# Netscale48HD_RS4850.net
KiCad netlist of a schematic drawn in Altium Designer
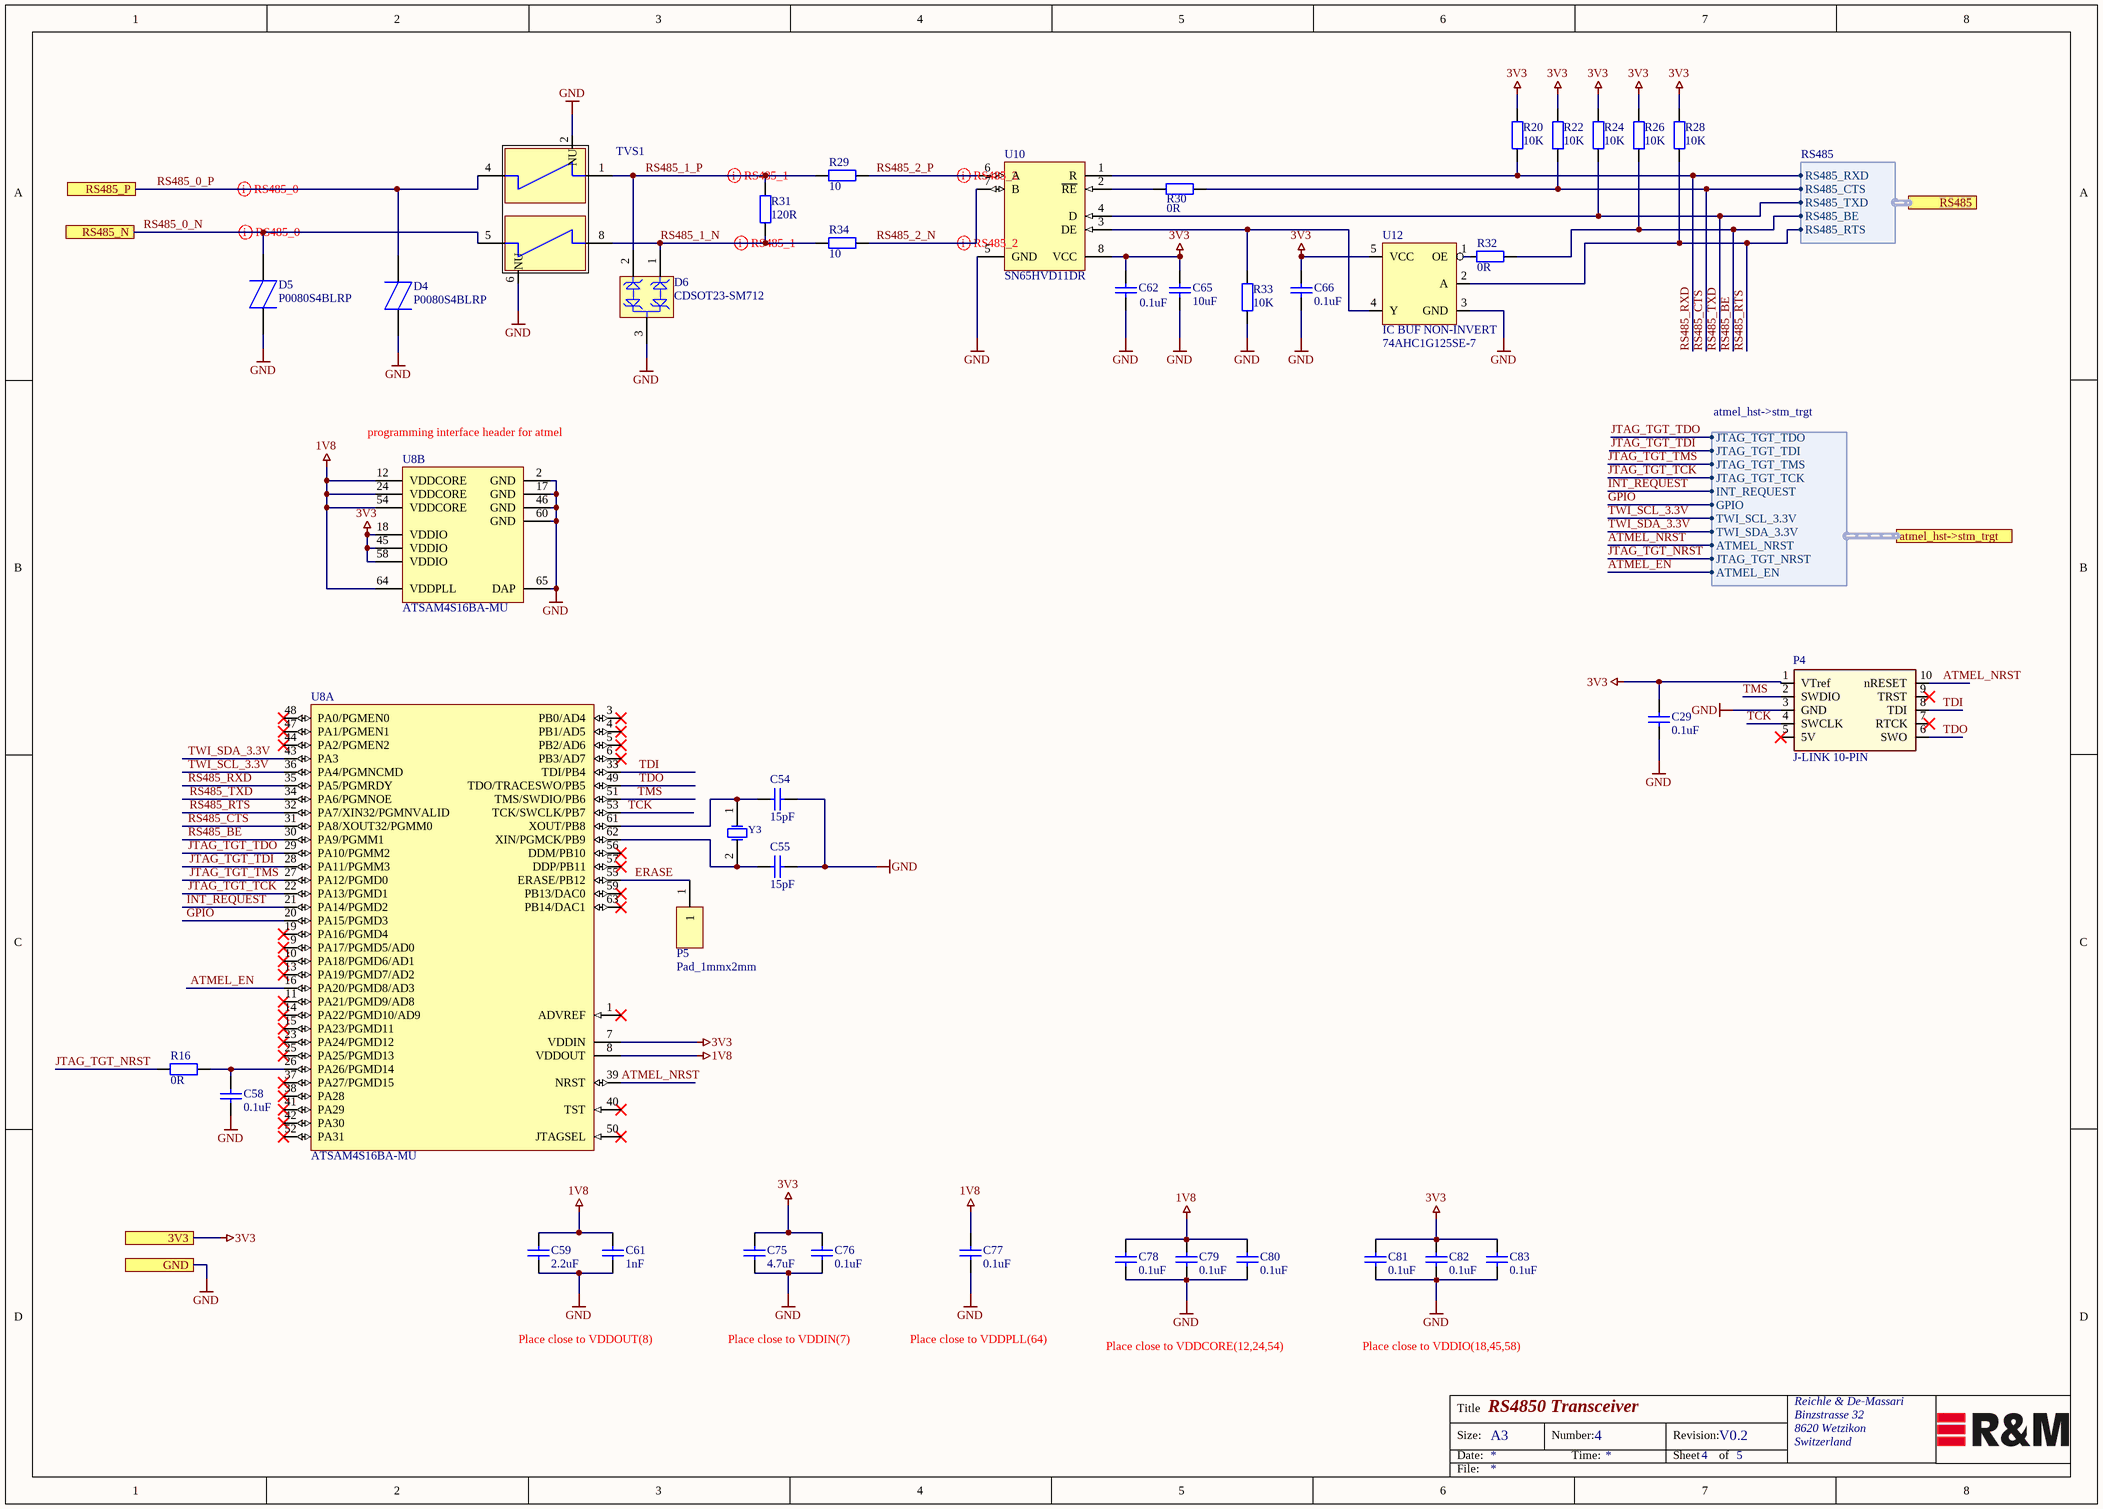
[diagram p0: Netscale48HD_RS4850.SchDoc]

(export (version "E")
  (design (tool "Eeschema 10.0.6"))
  (components
    (comp (ref "C29")
      (value "0.1uF")
      (footprint "Ceramic Capacitor 0402 EIA")
      (description "SMD/SMT WCAP-CSGP 0.1uF 0402 20% 10V MLCC")
      (fields (field (name "TOLERANCE") "20%") (field (name "VOLTAGE") "10VDC"))
      (libsource (lib "RDM_ALT_SCH") (part "Cap_0.1uF_0402"))
    )
    (comp (ref "C54")
      (value "15pF")
      (footprint "Ceramic Capacitor 0402 EIA")
      (description "Multilayer Ceramic Capacitors MLCC")
      (fields (field (name "TOLERANCE") "±1%") (field (name "VOLTAGE") "50V"))
      (libsource (lib "RDM_ALT_SCH") (part "Cap_15pF_0402"))
    )
    (comp (ref "C55")
      (value "15pF")
      (footprint "Ceramic Capacitor 0402 EIA")
      (description "Multilayer Ceramic Capacitors MLCC")
      (fields (field (name "TOLERANCE") "±1%") (field (name "VOLTAGE") "50V"))
      (libsource (lib "RDM_ALT_SCH") (part "Cap_15pF_0402"))
    )
    (comp (ref "C58")
      (value "0.1uF")
      (footprint "Ceramic Capacitor 0402 EIA")
      (description "SMD/SMT WCAP-CSGP 0.1uF 0402 20% 10V MLCC")
      (fields (field (name "TOLERANCE") "20%") (field (name "VOLTAGE") "10VDC"))
      (libsource (lib "RDM_ALT_SCH") (part "Cap_0.1uF_0402"))
    )
    (comp (ref "C59")
      (value "2.2uF")
      (footprint "Ceramic Capacitor 0402 EIA")
      (description "2.2µF ±20% 25V Ceramic Capacitor X5R 0402 (1005 Metric)")
      (fields (field (name "TOLERANCE") "±20%") (field (name "VOLTAGE") "25V"))
      (libsource (lib "RDM_ALT_SCH") (part "Cap_2.2uF_0402"))
    )
    (comp (ref "C61")
      (value "1nF")
      (footprint "Ceramic Capacitor 0402 EIA")
      (description "1000pF ±20% 50V Ceramic Capacitor X5R 0402 (1005 Metric)")
      (fields (field (name "TOLERANCE") "±20%") (field (name "VOLTAGE") "50V"))
      (libsource (lib "RDM_ALT_SCH") (part "Cap_1nF_0402"))
    )
    (comp (ref "C62")
      (value "0.1uF")
      (footprint "Ceramic Capacitor 0402 EIA")
      (description "SMD/SMT WCAP-CSGP 0.1uF 0402 20% 10V MLCC")
      (fields (field (name "TOLERANCE") "20%") (field (name "VOLTAGE") "10VDC"))
      (libsource (lib "RDM_Altium_Library") (part "Cap_0.1uF_0402"))
    )
    (comp (ref "C65")
      (value "10uF")
      (footprint "Ceramic Capacitor 0402 EIA")
      (description "Multilayer Ceramic Capacitors MLCC - SMD/SMT")
      (fields (field (name "TOLERANCE") "20%") (field (name "VOLTAGE") "10VDC"))
      (libsource (lib "RDM_Altium_Library") (part "Cap_10uF_0402"))
    )
    (comp (ref "C66")
      (value "0.1uF")
      (footprint "Ceramic Capacitor 0402 EIA")
      (description "SMD/SMT WCAP-CSGP 0.1uF 0402 20% 10V MLCC")
      (fields (field (name "TOLERANCE") "20%") (field (name "VOLTAGE") "10VDC"))
      (libsource (lib "RDM_Altium_Library") (part "Cap_0.1uF_0402"))
    )
    (comp (ref "C75")
      (value "4.7uF")
      (footprint "Ceramic Capacitor 0603 EIA")
      (description "SMD/SMT 0603 4.7uF 10volts")
      (fields (field (name "TOLERANCE") "20%") (field (name "VOLTAGE") "10VDC"))
      (libsource (lib "RDM_ALT_SCH") (part "Cap_4.7uF_0603"))
    )
    (comp (ref "C76")
      (value "0.1uF")
      (footprint "Ceramic Capacitor 0402 EIA")
      (description "SMD/SMT WCAP-CSGP 0.1uF 0402 20% 10V MLCC")
      (fields (field (name "TOLERANCE") "20%") (field (name "VOLTAGE") "10VDC"))
      (libsource (lib "RDM_ALT_SCH") (part "Cap_0.1uF_0402"))
    )
    (comp (ref "C77")
      (value "0.1uF")
      (footprint "Ceramic Capacitor 0402 EIA")
      (description "SMD/SMT WCAP-CSGP 0.1uF 0402 20% 10V MLCC")
      (fields (field (name "TOLERANCE") "20%") (field (name "VOLTAGE") "10VDC"))
      (libsource (lib "RDM_ALT_SCH") (part "Cap_0.1uF_0402"))
    )
    (comp (ref "C78")
      (value "0.1uF")
      (footprint "Ceramic Capacitor 0402 EIA")
      (description "SMD/SMT WCAP-CSGP 0.1uF 0402 20% 10V MLCC")
      (fields (field (name "TOLERANCE") "20%") (field (name "VOLTAGE") "10VDC"))
      (libsource (lib "RDM_ALT_SCH") (part "Cap_0.1uF_0402"))
    )
    (comp (ref "C79")
      (value "0.1uF")
      (footprint "Ceramic Capacitor 0402 EIA")
      (description "SMD/SMT WCAP-CSGP 0.1uF 0402 20% 10V MLCC")
      (fields (field (name "TOLERANCE") "20%") (field (name "VOLTAGE") "10VDC"))
      (libsource (lib "RDM_ALT_SCH") (part "Cap_0.1uF_0402"))
    )
    (comp (ref "C80")
      (value "0.1uF")
      (footprint "Ceramic Capacitor 0402 EIA")
      (description "SMD/SMT WCAP-CSGP 0.1uF 0402 20% 10V MLCC")
      (fields (field (name "TOLERANCE") "20%") (field (name "VOLTAGE") "10VDC"))
      (libsource (lib "RDM_ALT_SCH") (part "Cap_0.1uF_0402"))
    )
    (comp (ref "C81")
      (value "0.1uF")
      (footprint "Ceramic Capacitor 0402 EIA")
      (description "SMD/SMT WCAP-CSGP 0.1uF 0402 20% 10V MLCC")
      (fields (field (name "TOLERANCE") "20%") (field (name "VOLTAGE") "10VDC"))
      (libsource (lib "RDM_ALT_SCH") (part "Cap_0.1uF_0402"))
    )
    (comp (ref "C82")
      (value "0.1uF")
      (footprint "Ceramic Capacitor 0402 EIA")
      (description "SMD/SMT WCAP-CSGP 0.1uF 0402 20% 10V MLCC")
      (fields (field (name "TOLERANCE") "20%") (field (name "VOLTAGE") "10VDC"))
      (libsource (lib "RDM_ALT_SCH") (part "Cap_0.1uF_0402"))
    )
    (comp (ref "C83")
      (value "0.1uF")
      (footprint "Ceramic Capacitor 0402 EIA")
      (description "SMD/SMT WCAP-CSGP 0.1uF 0402 20% 10V MLCC")
      (fields (field (name "TOLERANCE") "20%") (field (name "VOLTAGE") "10VDC"))
      (libsource (lib "RDM_ALT_SCH") (part "Cap_0.1uF_0402"))
    )
    (comp (ref "D4")
      (value "P0080S4BLRP")
      (footprint "P0080S4BLRP")
      (fields (field (name "MANUFACTURER") "Littelfuse") (field (name "MANUFACTURER PARTNR") "P0080S4BLRP"))
      (libsource (lib "RDM_ALT_SCH") (part "P0080S4BLRP"))
    )
    (comp (ref "D5")
      (value "P0080S4BLRP")
      (footprint "P0080S4BLRP")
      (fields (field (name "MANUFACTURER") "Littelfuse") (field (name "MANUFACTURER PARTNR") "P0080S4BLRP"))
      (libsource (lib "RDM_ALT_SCH") (part "P0080S4BLRP"))
    )
    (comp (ref "D6")
      (value "CDSOT23-SM712")
      (footprint "BOUR-SOT23-3_V")
      (description "Surface Mount TVS Diode, 17 A Ipp, -55 to 150 degC, 3-Pin SOT23, RoHS, Tape and Reel")
      (fields (field (name "MANUFACTURER") "Bourns"))
      (libsource (lib "RDM_ALT_SCH") (part "Surface Mount TVS Diode"))
    )
    (comp (ref "P4")
      (value "J-LINK 10-PIN")
      (footprint "CONN-SEGGER-10-PIN")
      (description "Segger, J-Link 10-pin Needle Adapter")
      (libsource (lib "RDM_ALT_SCH") (part "CONN_Segger_10_PIN"))
    )
    (comp (ref "P5")
      (value "Pad_1mmx2mm")
      (footprint "Pad_1mmx2mm")
      (libsource (lib "RDM_ALT_SCH") (part "Pad_1mmx2mm"))
    )
    (comp (ref "R16")
      (value "0R")
      (footprint "Resistor 0402 EIA")
      (description "0 Ohms Resistor 0402")
      (fields (field (name "POWER") "100mW") (field (name "MANUFACTURER") "Panasonic Electronic Components"))
      (libsource (lib "RDM_ALT_SCH") (part "Res_0R_0402"))
    )
    (comp (ref "R20")
      (value "10K")
      (footprint "Resistor 0402 EIA")
      (description "SMD 10K ohm 1% 50V General Purpose")
      (fields (field (name "TOLERANCE") "1%") (field (name "POWER") "63mW"))
      (libsource (lib "RDM_Altium_Library") (part "Res_10K_0402"))
    )
    (comp (ref "R22")
      (value "10K")
      (footprint "Resistor 0402 EIA")
      (description "SMD 10K ohm 1% 50V General Purpose")
      (fields (field (name "TOLERANCE") "1%") (field (name "POWER") "63mW"))
      (libsource (lib "RDM_Altium_Library") (part "Res_10K_0402"))
    )
    (comp (ref "R24")
      (value "10K")
      (footprint "Resistor 0402 EIA")
      (description "SMD 10K ohm 1% 50V General Purpose")
      (fields (field (name "TOLERANCE") "1%") (field (name "POWER") "63mW"))
      (libsource (lib "RDM_Altium_Library") (part "Res_10K_0402"))
    )
    (comp (ref "R26")
      (value "10K")
      (footprint "Resistor 0402 EIA")
      (description "SMD 10K ohm 1% 50V General Purpose")
      (fields (field (name "TOLERANCE") "1%") (field (name "POWER") "63mW"))
      (libsource (lib "RDM_Altium_Library") (part "Res_10K_0402"))
    )
    (comp (ref "R28")
      (value "10K")
      (footprint "Resistor 0402 EIA")
      (description "SMD 10K ohm 1% 50V General Purpose")
      (fields (field (name "TOLERANCE") "1%") (field (name "POWER") "63mW"))
      (libsource (lib "RDM_Altium_Library") (part "Res_10K_0402"))
    )
    (comp (ref "R29")
      (value "10")
      (footprint "RES-0603[1608] - RFL")
      (description "Thick Film Resistors - SMD 1/4watt 10ohms 1% High Power AEC-Q200")
      (fields (field (name "MANUFACTURER") "Vishay") (field (name "VOLTAGE") "75 V"))
      (libsource (lib "RDM_ALT_SCH") (part "Res_10R_0603(1608)"))
    )
    (comp (ref "R30")
      (value "0R")
      (footprint "Resistor 0402 EIA")
      (description "0 Ohms Jumper 0.1W, 1/10W Chip Resistor 0402 (1005 Metric) Automotive AEC-Q200 Thick Film")
      (fields (field (name "POWER") "100mW") (field (name "MANUFACTURER") "Panasonic Electronic Components"))
      (libsource (lib "RDM_Altium_Library") (part "Res_0R_0402"))
    )
    (comp (ref "R31")
      (value "120R")
      (footprint "RES-0402[1005] - RFL")
      (fields
        (field (name "TOLERANCE") "1%")
        (field (name "MANUFACTURER") "TE Connectivity")
        (field (name "POWER") "0.063W")
      )
      (libsource (lib "RDM_ALT_SCH") (part "PassResBas0402-00405-A.3"))
    )
    (comp (ref "R32")
      (value "0R")
      (footprint "Resistor 0402 EIA")
      (description "0 Ohms Jumper 0.1W, 1/10W Chip Resistor 0402 (1005 Metric) Automotive AEC-Q200 Thick Film")
      (fields (field (name "POWER") "100mW") (field (name "MANUFACTURER") "Panasonic Electronic Components"))
      (libsource (lib "RDM_Altium_Library") (part "Res_0R_0402"))
    )
    (comp (ref "R33")
      (value "10K")
      (footprint "Resistor 0402 EIA")
      (description "SMD 10K ohm 1% 50V General Purpose")
      (fields (field (name "TOLERANCE") "1%") (field (name "POWER") "63mW"))
      (libsource (lib "RDM_Altium_Library") (part "Res_10K_0402"))
    )
    (comp (ref "R34")
      (value "10")
      (footprint "RES-0603[1608] - RFL")
      (description "Thick Film Resistors - SMD 1/4watt 10ohms 1% High Power AEC-Q200")
      (fields (field (name "MANUFACTURER") "Vishay") (field (name "VOLTAGE") "75 V"))
      (libsource (lib "RDM_ALT_SCH") (part "Res_10R_0603(1608)"))
    )
    (comp (ref "TVS1")
      (value "TBU-CA065-200-WH")
      (footprint "Bourns_TBU_PL060_WH")
      (description "TBU-PL Series dual 50 ohm Surge Suppressors, bi-directional")
      (fields (field (name "MANUFACTURER") "Bourns"))
      (libsource (lib "RDM_ALT_SCH") (part "Bourns_TBU-PL060-200-WH"))
    )
    (comp (ref "U8")
      (value "ATSAM4S16BA-MU")
      (footprint "64PS_N")
      (fields (field (name "MANUFACTURER") "Atmel"))
      (libsource (lib "RDM_ALT_SCH") (part "ATSAM4S16BA-MU"))
    )
    (comp (ref "U10")
      (value "SN65HVD11DR")
      (footprint "TI_D (R-PDSO-G8)_8_R")
      (description "1/1 Transceiver Half RS422, RS485 8-SOIC")
      (fields (field (name "MANUFACTURER") "TI"))
      (libsource (lib "RDM_ALT_SCH") (part "RS_485 Transceivers"))
    )
    (comp (ref "U12")
      (value "IC BUF NON-INVERT")
      (footprint "SOT353")
      (description "Buffer, Non-Inverting 1 Element 1 Bit per Element 3-State Output SOT-353")
      (fields
        (field (name "MANUFACTURER") "Diodes Incorporated")
        (field (name "MANUFACTURER PARTNR") "74AHC1G125SE-7")
      )
      (libsource (lib "RDM_ALT_SCH") (part "74AHC1G125SE-7"))
    )
    (comp (ref "Y3")
      (value "ABM3-12.000MHZ-B2-T")
      (footprint "ABM3-12.000MHZ-B2-T")
      (description "12MHz ±20ppm Crystal 18pF 60 Ohms 2-SMD, No Lead")
      (fields (field (name "MANUFACTURER") "Abracon LLC"))
      (libsource (lib "RDM_ALT_SCH") (part "CRYSTAL_2Pin_ABM3-12.000MHZ-B2-T"))
    )
  )
  (nets
    (net (code "3") (name "/ATMEL_EN") (class "Default")
      (node (ref "U8") (pin "16") (pinfunction "PA20/PGMD8/AD3_16") (pintype "bidirectional"))
    )
    (net (code "4") (name "/ATMEL_NRST") (class "Default")
      (node (ref "P4") (pin "10") (pinfunction "nRESET_10") (pintype "passive"))
      (node (ref "U8") (pin "39") (pinfunction "NRST_39") (pintype "bidirectional"))
    )
    (net (code "5") (name "/ERASE") (class "Default")
      (node (ref "P5") (pin "1") (pinfunction "1_1") (pintype "passive"))
      (node (ref "U8") (pin "55") (pinfunction "ERASE/PB12_55") (pintype "bidirectional"))
    )
    (net (code "6") (name "/GPIO") (class "Default")
      (node (ref "U8") (pin "20") (pinfunction "PA15/PGMD3_20") (pintype "bidirectional"))
    )
    (net (code "7") (name "/INT_REQUEST") (class "Default")
      (node (ref "U8") (pin "21") (pinfunction "PA14/PGMD2_21") (pintype "bidirectional"))
    )
    (net (code "8") (name "/JTAG_TGT_NRST") (class "Default")
      (node (ref "R16") (pin "1") (pinfunction "1_1") (pintype "passive"))
    )
    (net (code "9") (name "/JTAG_TGT_TCK") (class "Default")
      (node (ref "U8") (pin "22") (pinfunction "PA13/PGMD1_22") (pintype "bidirectional"))
    )
    (net (code "10") (name "/JTAG_TGT_TDI") (class "Default")
      (node (ref "U8") (pin "28") (pinfunction "PA11/PGMM3_28") (pintype "bidirectional"))
    )
    (net (code "11") (name "/JTAG_TGT_TDO") (class "Default")
      (node (ref "U8") (pin "29") (pinfunction "PA10/PGMM2_29") (pintype "bidirectional"))
    )
    (net (code "12") (name "/JTAG_TGT_TMS") (class "Default")
      (node (ref "U8") (pin "27") (pinfunction "PA12/PGMD0_27") (pintype "bidirectional"))
    )
    (net (code "13") (name "/RS485_0_N") (class "Default")
      (node (ref "D5") (pin "2") (pinfunction "K_2") (pintype "passive"))
      (node (ref "TVS1") (pin "5") (pinfunction "5_5") (pintype "passive"))
    )
    (net (code "14") (name "/RS485_0_P") (class "Default")
      (node (ref "D4") (pin "2") (pinfunction "K_2") (pintype "passive"))
      (node (ref "TVS1") (pin "4") (pinfunction "4_4") (pintype "passive"))
    )
    (net (code "15") (name "/RS485_1_N") (class "Default")
      (node (ref "D6") (pin "1") (pinfunction "1_1") (pintype "passive"))
      (node (ref "R31") (pin "2") (pinfunction "2_2") (pintype "passive"))
      (node (ref "R34") (pin "2") (pinfunction "2_2") (pintype "passive"))
      (node (ref "TVS1") (pin "8") (pintype "passive"))
    )
    (net (code "16") (name "/RS485_1_P") (class "Default")
      (node (ref "D6") (pin "2") (pinfunction "2_2") (pintype "passive"))
      (node (ref "R29") (pin "2") (pinfunction "2_2") (pintype "passive"))
      (node (ref "R31") (pin "1") (pinfunction "1_1") (pintype "passive"))
      (node (ref "TVS1") (pin "1") (pinfunction "1_1") (pintype "passive"))
    )
    (net (code "17") (name "/RS485_2_N") (class "Default")
      (node (ref "R34") (pin "1") (pinfunction "1_1") (pintype "passive"))
      (node (ref "U10") (pin "7") (pinfunction "B_7") (pintype "bidirectional"))
    )
    (net (code "18") (name "/RS485_2_P") (class "Default")
      (node (ref "R29") (pin "1") (pinfunction "1_1") (pintype "passive"))
      (node (ref "U10") (pin "6") (pinfunction "A_6") (pintype "bidirectional"))
    )
    (net (code "19") (name "/RS485_BE") (class "Default")
      (node (ref "R26") (pin "1") (pinfunction "1_1") (pintype "passive"))
      (node (ref "R32") (pin "2") (pinfunction "2_2") (pintype "passive"))
      (node (ref "U8") (pin "30") (pinfunction "PA9/PGMM1_30") (pintype "bidirectional"))
    )
    (net (code "20") (name "/RS485_CTS") (class "Default")
      (node (ref "R22") (pin "1") (pinfunction "1_1") (pintype "passive"))
      (node (ref "R30") (pin "2") (pinfunction "2_2") (pintype "passive"))
      (node (ref "U8") (pin "31") (pinfunction "PA8/XOUT32/PGMM0_31") (pintype "bidirectional"))
    )
    (net (code "21") (name "/RS485_RTS") (class "Default")
      (node (ref "R28") (pin "1") (pinfunction "1_1") (pintype "passive"))
      (node (ref "U12") (pin "2") (pinfunction "A_2") (pintype "passive"))
      (node (ref "U8") (pin "32") (pinfunction "PA7/XIN32/PGMNVALID_32") (pintype "bidirectional"))
    )
    (net (code "22") (name "/RS485_RXD") (class "Default")
      (node (ref "R20") (pin "1") (pinfunction "1_1") (pintype "passive"))
      (node (ref "U10") (pin "1") (pinfunction "R_1") (pintype "tri_state"))
      (node (ref "U8") (pin "35") (pinfunction "PA5/PGMRDY_35") (pintype "bidirectional"))
    )
    (net (code "23") (name "/RS485_TXD") (class "Default")
      (node (ref "R24") (pin "1") (pinfunction "1_1") (pintype "passive"))
      (node (ref "U10") (pin "4") (pinfunction "D_4") (pintype "input"))
      (node (ref "U8") (pin "34") (pinfunction "PA6/PGMNOE_34") (pintype "bidirectional"))
    )
    (net (code "24") (name "/TCK") (class "Default")
      (node (ref "P4") (pin "4") (pinfunction "SWCLK_4") (pintype "passive"))
      (node (ref "U8") (pin "53") (pinfunction "TCK/SWCLK/PB7_53") (pintype "bidirectional"))
    )
    (net (code "25") (name "/TDI") (class "Default")
      (node (ref "P4") (pin "8") (pinfunction "TDI_8") (pintype "passive"))
      (node (ref "U8") (pin "33") (pinfunction "TDI/PB4_33") (pintype "bidirectional"))
    )
    (net (code "26") (name "/TDO") (class "Default")
      (node (ref "P4") (pin "6") (pinfunction "SWO_6") (pintype "passive"))
      (node (ref "U8") (pin "49") (pinfunction "TDO/TRACESWO/PB5_49") (pintype "bidirectional"))
    )
    (net (code "27") (name "/TMS") (class "Default")
      (node (ref "P4") (pin "2") (pinfunction "SWDIO_2") (pintype "passive"))
      (node (ref "U8") (pin "51") (pinfunction "TMS/SWDIO/PB6_51") (pintype "bidirectional"))
    )
    (net (code "28") (name "/TWI_SCL_3.3V") (class "Default")
      (node (ref "U8") (pin "36") (pinfunction "PA4/PGMNCMD_36") (pintype "bidirectional"))
    )
    (net (code "29") (name "/TWI_SDA_3.3V") (class "Default")
      (node (ref "U8") (pin "43") (pinfunction "PA3_43") (pintype "bidirectional"))
    )
    (net (code "32") (name "1V8") (class "Default")
      (node (ref "C59") (pin "2") (pinfunction "2_2") (pintype "passive"))
      (node (ref "C61") (pin "2") (pinfunction "2_2") (pintype "passive"))
      (node (ref "C77") (pin "2") (pinfunction "2_2") (pintype "passive"))
      (node (ref "C78") (pin "2") (pinfunction "2_2") (pintype "passive"))
      (node (ref "C79") (pin "2") (pinfunction "2_2") (pintype "passive"))
      (node (ref "C80") (pin "2") (pinfunction "2_2") (pintype "passive"))
      (node (ref "U8") (pin "12") (pinfunction "VDDCORE_12") (pintype "power_in"))
      (node (ref "U8") (pin "24") (pinfunction "VDDCORE_24") (pintype "power_in"))
      (node (ref "U8") (pin "54") (pinfunction "VDDCORE_54") (pintype "power_in"))
      (node (ref "U8") (pin "64") (pinfunction "VDDPLL_64") (pintype "power_in"))
      (node (ref "U8") (pin "8") (pinfunction "VDDOUT_8") (pintype "power_in"))
    )
    (net (code "33") (name "3V3") (class "Default")
      (node (ref "C29") (pin "2") (pinfunction "2_2") (pintype "passive"))
      (node (ref "C62") (pin "1") (pinfunction "1_1") (pintype "passive"))
      (node (ref "C65") (pin "2") (pinfunction "2_2") (pintype "passive"))
      (node (ref "C66") (pin "1") (pinfunction "1_1") (pintype "passive"))
      (node (ref "C75") (pin "2") (pinfunction "2_2") (pintype "passive"))
      (node (ref "C76") (pin "2") (pinfunction "2_2") (pintype "passive"))
      (node (ref "C81") (pin "2") (pinfunction "2_2") (pintype "passive"))
      (node (ref "C82") (pin "2") (pinfunction "2_2") (pintype "passive"))
      (node (ref "C83") (pin "2") (pinfunction "2_2") (pintype "passive"))
      (node (ref "P4") (pin "1") (pinfunction "VTref_1") (pintype "passive"))
      (node (ref "R20") (pin "2") (pinfunction "2_2") (pintype "passive"))
      (node (ref "R22") (pin "2") (pinfunction "2_2") (pintype "passive"))
      (node (ref "R24") (pin "2") (pinfunction "2_2") (pintype "passive"))
      (node (ref "R26") (pin "2") (pinfunction "2_2") (pintype "passive"))
      (node (ref "R28") (pin "2") (pinfunction "2_2") (pintype "passive"))
      (node (ref "U10") (pin "8") (pinfunction "VCC_8") (pintype "power_in"))
      (node (ref "U12") (pin "5") (pinfunction "VCC_5") (pintype "passive"))
      (node (ref "U8") (pin "18") (pinfunction "VDDIO_18") (pintype "power_in"))
      (node (ref "U8") (pin "45") (pinfunction "VDDIO_45") (pintype "power_in"))
      (node (ref "U8") (pin "58") (pinfunction "VDDIO_58") (pintype "power_in"))
      (node (ref "U8") (pin "7") (pinfunction "VDDIN_7") (pintype "power_in"))
    )
    (net (code "34") (name "GND") (class "Default")
      (node (ref "C29") (pin "1") (pinfunction "1_1") (pintype "passive"))
      (node (ref "C54") (pin "1") (pinfunction "1_1") (pintype "passive"))
      (node (ref "C55") (pin "1") (pinfunction "1_1") (pintype "passive"))
      (node (ref "C58") (pin "1") (pinfunction "1_1") (pintype "passive"))
      (node (ref "C59") (pin "1") (pinfunction "1_1") (pintype "passive"))
      (node (ref "C61") (pin "1") (pinfunction "1_1") (pintype "passive"))
      (node (ref "C62") (pin "2") (pinfunction "2_2") (pintype "passive"))
      (node (ref "C65") (pin "1") (pinfunction "1_1") (pintype "passive"))
      (node (ref "C66") (pin "2") (pinfunction "2_2") (pintype "passive"))
      (node (ref "C75") (pin "1") (pinfunction "1_1") (pintype "passive"))
      (node (ref "C76") (pin "1") (pinfunction "1_1") (pintype "passive"))
      (node (ref "C77") (pin "1") (pinfunction "1_1") (pintype "passive"))
      (node (ref "C78") (pin "1") (pinfunction "1_1") (pintype "passive"))
      (node (ref "C79") (pin "1") (pinfunction "1_1") (pintype "passive"))
      (node (ref "C80") (pin "1") (pinfunction "1_1") (pintype "passive"))
      (node (ref "C81") (pin "1") (pinfunction "1_1") (pintype "passive"))
      (node (ref "C82") (pin "1") (pinfunction "1_1") (pintype "passive"))
      (node (ref "C83") (pin "1") (pinfunction "1_1") (pintype "passive"))
      (node (ref "D4") (pin "1") (pinfunction "A_1") (pintype "passive"))
      (node (ref "D5") (pin "1") (pinfunction "A_1") (pintype "passive"))
      (node (ref "D6") (pin "3") (pinfunction "3_3") (pintype "passive"))
      (node (ref "P4") (pin "3") (pinfunction "GND_3") (pintype "passive"))
      (node (ref "R33") (pin "1") (pinfunction "1_1") (pintype "passive"))
      (node (ref "TVS1") (pin "2") (pinfunction "NU_2") (pintype "passive"))
      (node (ref "TVS1") (pin "6") (pinfunction "NU_6") (pintype "passive"))
      (node (ref "U10") (pin "5") (pinfunction "GND_5") (pintype "power_in"))
      (node (ref "U12") (pin "3") (pinfunction "GND_3") (pintype "passive"))
      (node (ref "U8") (pin "17") (pinfunction "GND_17") (pintype "power_in"))
      (node (ref "U8") (pin "2") (pinfunction "GND_2") (pintype "power_in"))
      (node (ref "U8") (pin "46") (pinfunction "GND_46") (pintype "power_in"))
      (node (ref "U8") (pin "60") (pinfunction "GND_60") (pintype "power_in"))
      (node (ref "U8") (pin "65") (pinfunction "DAP_65") (pintype "power_in"))
    )
    (net (code "35") (name "Net-(U8A-PA26{slash}PGMD14)") (class "Default")
      (node (ref "C58") (pin "2") (pinfunction "2_2") (pintype "passive"))
      (node (ref "R16") (pin "2") (pinfunction "2_2") (pintype "passive"))
      (node (ref "U8") (pin "26") (pinfunction "PA26/PGMD14_26") (pintype "bidirectional"))
    )
    (net (code "36") (name "Net-(U8A-XIN{slash}PGMCK{slash}PB9)") (class "Default")
      (node (ref "C55") (pin "2") (pinfunction "2_2") (pintype "passive"))
      (node (ref "U8") (pin "62") (pinfunction "XIN/PGMCK/PB9_62") (pintype "bidirectional"))
      (node (ref "Y3") (pin "2") (pinfunction "OSC2_2") (pintype "passive"))
    )
    (net (code "37") (name "Net-(U8A-XOUT{slash}PB8)") (class "Default")
      (node (ref "C54") (pin "2") (pinfunction "2_2") (pintype "passive"))
      (node (ref "U8") (pin "61") (pinfunction "XOUT/PB8_61") (pintype "bidirectional"))
      (node (ref "Y3") (pin "1") (pinfunction "OSC1_1") (pintype "passive"))
    )
    (net (code "38") (name "Net-(U10-DE)") (class "Default")
      (node (ref "R33") (pin "2") (pinfunction "2_2") (pintype "passive"))
      (node (ref "U10") (pin "3") (pinfunction "DE_3") (pintype "input"))
      (node (ref "U12") (pin "4") (pinfunction "Y_4") (pintype "passive"))
    )
    (net (code "39") (name "Net-(U10-~{RE})") (class "Default")
      (node (ref "R30") (pin "1") (pinfunction "1_1") (pintype "passive"))
      (node (ref "U10") (pin "2") (pinfunction "~{RE}_2") (pintype "input"))
    )
    (net (code "40") (name "Net-(U12-OE)") (class "Default")
      (node (ref "R32") (pin "1") (pinfunction "1_1") (pintype "passive"))
      (node (ref "U12") (pin "1") (pinfunction "OE_1") (pintype "passive"))
    )
    (net (code "41") (name "unconnected-(P4-5V-Pad5)") (class "Default")
      (node (ref "P4") (pin "5") (pinfunction "5V_5") (pintype "passive+no_connect"))
    )
    (net (code "42") (name "unconnected-(P4-RTCK-Pad7)") (class "Default")
      (node (ref "P4") (pin "7") (pinfunction "RTCK_7") (pintype "passive+no_connect"))
    )
    (net (code "43") (name "unconnected-(P4-TRST-Pad9)") (class "Default")
      (node (ref "P4") (pin "9") (pinfunction "TRST_9") (pintype "passive+no_connect"))
    )
    (net (code "44") (name "unconnected-(U8A-ADVREF-Pad1)") (class "Default")
      (node (ref "U8") (pin "1") (pinfunction "ADVREF_1") (pintype "input+no_connect"))
    )
    (net (code "45") (name "unconnected-(U8A-DDM{slash}PB10-Pad56)") (class "Default")
      (node (ref "U8") (pin "56") (pinfunction "DDM/PB10_56") (pintype "bidirectional+no_connect"))
    )
    (net (code "46") (name "unconnected-(U8A-DDP{slash}PB11-Pad57)") (class "Default")
      (node (ref "U8") (pin "57") (pinfunction "DDP/PB11_57") (pintype "bidirectional+no_connect"))
    )
    (net (code "47") (name "unconnected-(U8A-JTAGSEL-Pad50)") (class "Default")
      (node (ref "U8") (pin "50") (pinfunction "JTAGSEL_50") (pintype "input+no_connect"))
    )
    (net (code "48") (name "unconnected-(U8A-PA0{slash}PGMEN0-Pad48)") (class "Default")
      (node (ref "U8") (pin "48") (pinfunction "PA0/PGMEN0_48") (pintype "bidirectional+no_connect"))
    )
    (net (code "49") (name "unconnected-(U8A-PA1{slash}PGMEN1-Pad47)") (class "Default")
      (node (ref "U8") (pin "47") (pinfunction "PA1/PGMEN1_47") (pintype "bidirectional+no_connect"))
    )
    (net (code "50") (name "unconnected-(U8A-PA2{slash}PGMEN2-Pad44)") (class "Default")
      (node (ref "U8") (pin "44") (pinfunction "PA2/PGMEN2_44") (pintype "bidirectional+no_connect"))
    )
    (net (code "51") (name "unconnected-(U8A-PA16{slash}PGMD4-Pad19)") (class "Default")
      (node (ref "U8") (pin "19") (pinfunction "PA16/PGMD4_19") (pintype "bidirectional+no_connect"))
    )
    (net (code "52") (name "unconnected-(U8A-PA17{slash}PGMD5{slash}AD0-Pad9)") (class "Default")
      (node (ref "U8") (pin "9") (pinfunction "PA17/PGMD5/AD0_9") (pintype "bidirectional+no_connect"))
    )
    (net (code "53") (name "unconnected-(U8A-PA18{slash}PGMD6{slash}AD1-Pad10)") (class "Default")
      (node (ref "U8") (pin "10") (pinfunction "PA18/PGMD6/AD1_10") (pintype "bidirectional+no_connect"))
    )
    (net (code "54") (name "unconnected-(U8A-PA19{slash}PGMD7{slash}AD2-Pad13)") (class "Default")
      (node (ref "U8") (pin "13") (pinfunction "PA19/PGMD7/AD2_13") (pintype "bidirectional+no_connect"))
    )
    (net (code "55") (name "unconnected-(U8A-PA21{slash}PGMD9{slash}AD8-Pad11)") (class "Default")
      (node (ref "U8") (pin "11") (pinfunction "PA21/PGMD9/AD8_11") (pintype "bidirectional+no_connect"))
    )
    (net (code "56") (name "unconnected-(U8A-PA22{slash}PGMD10{slash}AD9-Pad14)") (class "Default")
      (node (ref "U8") (pin "14") (pinfunction "PA22/PGMD10/AD9_14") (pintype "bidirectional+no_connect"))
    )
    (net (code "57") (name "unconnected-(U8A-PA23{slash}PGMD11-Pad15)") (class "Default")
      (node (ref "U8") (pin "15") (pinfunction "PA23/PGMD11_15") (pintype "bidirectional+no_connect"))
    )
    (net (code "58") (name "unconnected-(U8A-PA24{slash}PGMD12-Pad23)") (class "Default")
      (node (ref "U8") (pin "23") (pinfunction "PA24/PGMD12_23") (pintype "bidirectional+no_connect"))
    )
    (net (code "59") (name "unconnected-(U8A-PA25{slash}PGMD13-Pad25)") (class "Default")
      (node (ref "U8") (pin "25") (pinfunction "PA25/PGMD13_25") (pintype "bidirectional+no_connect"))
    )
    (net (code "60") (name "unconnected-(U8A-PA27{slash}PGMD15-Pad37)") (class "Default")
      (node (ref "U8") (pin "37") (pinfunction "PA27/PGMD15_37") (pintype "bidirectional+no_connect"))
    )
    (net (code "61") (name "unconnected-(U8A-PA28-Pad38)") (class "Default")
      (node (ref "U8") (pin "38") (pinfunction "PA28_38") (pintype "bidirectional+no_connect"))
    )
    (net (code "62") (name "unconnected-(U8A-PA29-Pad41)") (class "Default")
      (node (ref "U8") (pin "41") (pinfunction "PA29_41") (pintype "bidirectional+no_connect"))
    )
    (net (code "63") (name "unconnected-(U8A-PA30-Pad42)") (class "Default")
      (node (ref "U8") (pin "42") (pinfunction "PA30_42") (pintype "bidirectional+no_connect"))
    )
    (net (code "64") (name "unconnected-(U8A-PA31-Pad52)") (class "Default")
      (node (ref "U8") (pin "52") (pinfunction "PA31_52") (pintype "bidirectional+no_connect"))
    )
    (net (code "65") (name "unconnected-(U8A-PB0{slash}AD4-Pad3)") (class "Default")
      (node (ref "U8") (pin "3") (pinfunction "PB0/AD4_3") (pintype "bidirectional+no_connect"))
    )
    (net (code "66") (name "unconnected-(U8A-PB1{slash}AD5-Pad4)") (class "Default")
      (node (ref "U8") (pin "4") (pinfunction "PB1/AD5_4") (pintype "bidirectional+no_connect"))
    )
    (net (code "67") (name "unconnected-(U8A-PB2{slash}AD6-Pad5)") (class "Default")
      (node (ref "U8") (pin "5") (pinfunction "PB2/AD6_5") (pintype "bidirectional+no_connect"))
    )
    (net (code "68") (name "unconnected-(U8A-PB3{slash}AD7-Pad6)") (class "Default")
      (node (ref "U8") (pin "6") (pinfunction "PB3/AD7_6") (pintype "bidirectional+no_connect"))
    )
    (net (code "69") (name "unconnected-(U8A-PB13{slash}DAC0-Pad59)") (class "Default")
      (node (ref "U8") (pin "59") (pinfunction "PB13/DAC0_59") (pintype "bidirectional+no_connect"))
    )
    (net (code "70") (name "unconnected-(U8A-PB14{slash}DAC1-Pad63)") (class "Default")
      (node (ref "U8") (pin "63") (pinfunction "PB14/DAC1_63") (pintype "bidirectional+no_connect"))
    )
    (net (code "71") (name "unconnected-(U8A-TST-Pad40)") (class "Default")
      (node (ref "U8") (pin "40") (pinfunction "TST_40") (pintype "input+no_connect"))
    )
  )
)
